# LoRa_Dev_A_1.net
KiCad netlist of a schematic drawn in EAGLE
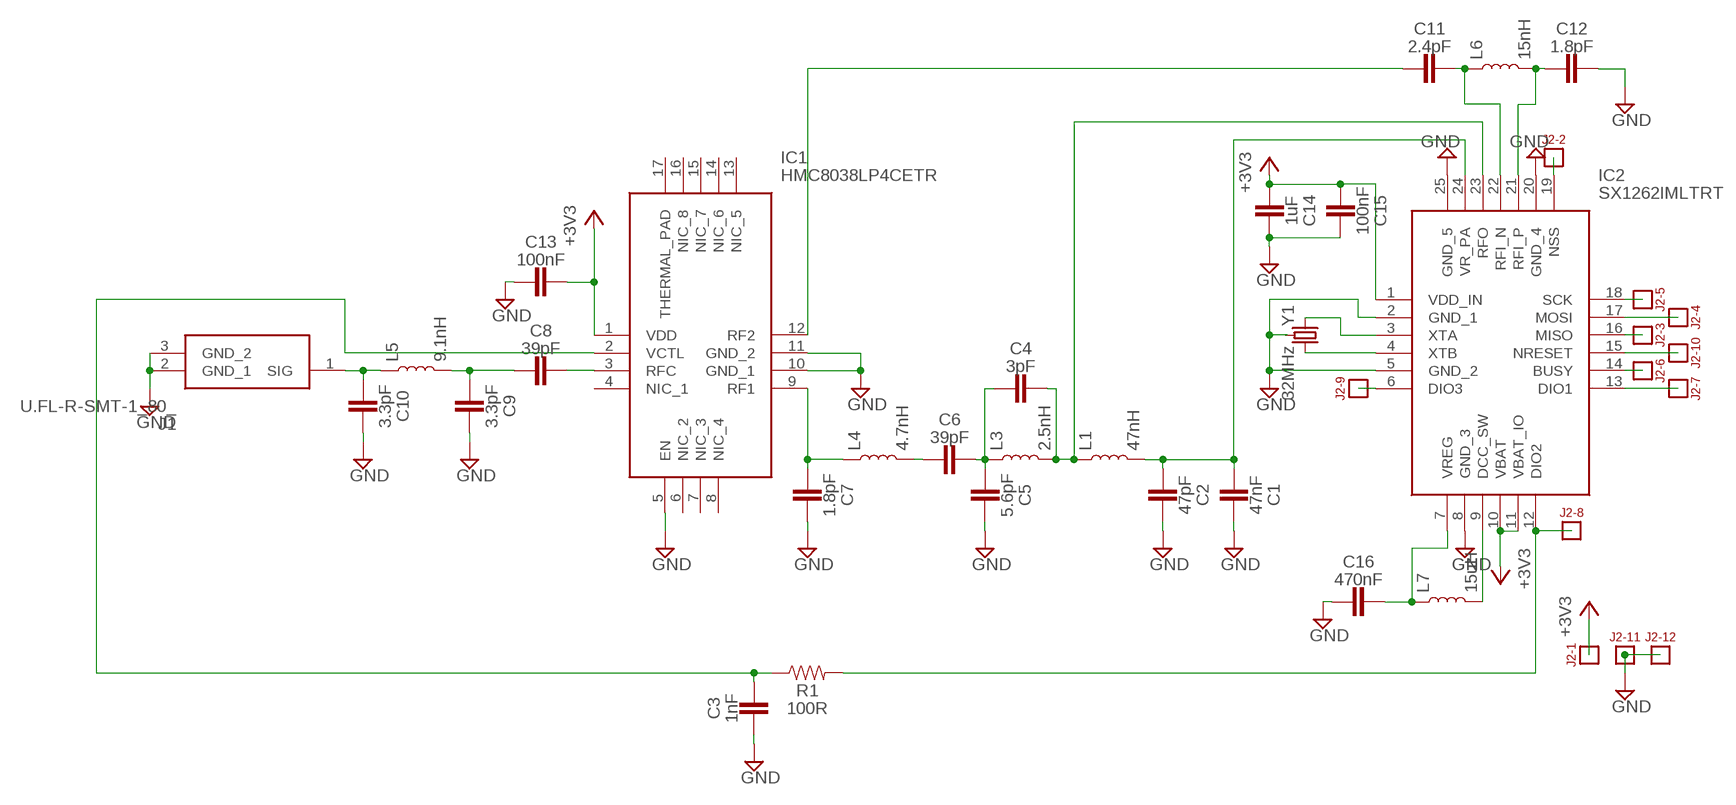
[diagram p0: schematic, sheet 1]

(export (version "E")
  (design (tool "Eeschema 10.0.6"))
  (components
    (comp (ref "C1")
      (value "47nF")
      (footprint "eagle-import:0603")
      (libsource (lib "eagle-import") (part "C_0603"))
    )
    (comp (ref "C2")
      (value "47pF")
      (footprint "eagle-import:0603")
      (libsource (lib "eagle-import") (part "C_0603"))
    )
    (comp (ref "C3")
      (value "1nF")
      (footprint "eagle-import:0603")
      (libsource (lib "eagle-import") (part "C_0603"))
    )
    (comp (ref "C4")
      (value "3pF")
      (footprint "eagle-import:0603")
      (libsource (lib "eagle-import") (part "C_0603"))
    )
    (comp (ref "C5")
      (value "5.6pF")
      (footprint "eagle-import:0402")
      (libsource (lib "eagle-import") (part "C_0402"))
    )
    (comp (ref "C6")
      (value "39pF")
      (footprint "eagle-import:0402")
      (libsource (lib "eagle-import") (part "C_0402"))
    )
    (comp (ref "C7")
      (value "1.8pF")
      (footprint "eagle-import:0402")
      (libsource (lib "eagle-import") (part "C_0402"))
    )
    (comp (ref "C8")
      (value "39pF")
      (footprint "eagle-import:0402")
      (libsource (lib "eagle-import") (part "C_0402"))
    )
    (comp (ref "C9")
      (value "3.3pF")
      (footprint "eagle-import:0402")
      (libsource (lib "eagle-import") (part "C_0402"))
    )
    (comp (ref "C10")
      (value "3.3pF")
      (footprint "eagle-import:0402")
      (libsource (lib "eagle-import") (part "C_0402"))
    )
    (comp (ref "C11")
      (value "2.4pF")
      (footprint "eagle-import:0402")
      (libsource (lib "eagle-import") (part "C_0402"))
    )
    (comp (ref "C12")
      (value "1.8pF")
      (footprint "eagle-import:0402")
      (libsource (lib "eagle-import") (part "C_0402"))
    )
    (comp (ref "C13")
      (value "100nF")
      (footprint "eagle-import:0402")
      (libsource (lib "eagle-import") (part "C_0402"))
    )
    (comp (ref "C14")
      (value "1uF")
      (footprint "eagle-import:0402")
      (libsource (lib "eagle-import") (part "C_0402"))
    )
    (comp (ref "C15")
      (value "100nF")
      (footprint "eagle-import:0402")
      (libsource (lib "eagle-import") (part "C_0402"))
    )
    (comp (ref "C16")
      (value "470nF")
      (footprint "eagle-import:0402")
      (libsource (lib "eagle-import") (part "C_0402"))
    )
    (comp (ref "IC1")
      (value "HMC8038LP4CETR")
      (footprint "eagle-import:QFN65P400X400X90-17N")
      (fields (field (name "MOUSER_PART_NUMBER") "584-HMC8038LP4CETR"))
      (libsource (lib "eagle-import") (part "HMC8038LP4CETR"))
    )
    (comp (ref "IC2")
      (value "SX1262IMLTRT")
      (footprint "eagle-import:QFN50P400X400X100-25N")
      (fields (field (name "MOUSER_PART_NUMBER") "947-SX1262IMLTRT"))
      (libsource (lib "eagle-import") (part "SX1262IMLTRT"))
    )
    (comp (ref "J1")
      (value "U.FL-R-SMT-1_80_")
      (footprint "eagle-import:UFLRSMT180")
      (fields
        (field (name "MANUFACTURER_PART_NUMBER") "U.FL-R-SMT-1(80)")
        (field (name "MOUSER_PART_NUMBER") "798-UFLRSMT180")
      )
      (libsource (lib "eagle-import") (part "U.FL-R-SMT-1_80_"))
    )
    (comp (ref "J2")
      (value "HEADER_12PIN")
      (footprint "eagle-import:HEADER_12PIN")
      (libsource (lib "eagle-import") (part "HEADER_12PIN"))
    )
    (comp (ref "L1")
      (value "47nH")
      (footprint "eagle-import:0603")
      (libsource (lib "eagle-import") (part "L_0603"))
    )
    (comp (ref "L3")
      (value "2.5nH")
      (footprint "eagle-import:0402")
      (libsource (lib "eagle-import") (part "L_0402"))
    )
    (comp (ref "L4")
      (value "4.7nH")
      (footprint "eagle-import:0402")
      (libsource (lib "eagle-import") (part "L_0402"))
    )
    (comp (ref "L5")
      (value "9.1nH")
      (footprint "eagle-import:0402")
      (libsource (lib "eagle-import") (part "L_0402"))
    )
    (comp (ref "L6")
      (value "15nH")
      (footprint "eagle-import:0402")
      (libsource (lib "eagle-import") (part "L_0402"))
    )
    (comp (ref "L7")
      (value "15uH")
      (footprint "eagle-import:0805")
      (libsource (lib "eagle-import") (part "L_0805"))
    )
    (comp (ref "R1")
      (value "100R")
      (footprint "eagle-import:0402")
      (libsource (lib "eagle-import") (part "R_0402"))
    )
    (comp (ref "Y1")
      (value "32MHz")
      (footprint "eagle-import:SMD2016-4P")
      (libsource (lib "eagle-import") (part "XTAL_SMD2016-4P"))
    )
  )
  (nets
    (net (code "1") (name "+3V3") (class "Default")
      (node (ref "C13") (pin "2") (pinfunction "2_2") (pintype "passive"))
      (node (ref "C14") (pin "1") (pinfunction "1_1") (pintype "passive"))
      (node (ref "C15") (pin "1") (pinfunction "1_1") (pintype "passive"))
      (node (ref "IC1") (pin "1") (pinfunction "VDD_1") (pintype "bidirectional"))
      (node (ref "IC2") (pin "1") (pinfunction "VDD_IN_1") (pintype "input"))
      (node (ref "IC2") (pin "10") (pinfunction "VBAT_10") (pintype "input"))
      (node (ref "IC2") (pin "11") (pinfunction "VBAT_IO_11") (pintype "input"))
      (node (ref "J2") (pin "P$1") (pinfunction "P$1_P$1") (pintype "bidirectional"))
    )
    (net (code "2") (name "GND") (class "Default")
      (node (ref "C1") (pin "2") (pinfunction "2_2") (pintype "passive"))
      (node (ref "C10") (pin "2") (pinfunction "2_2") (pintype "passive"))
      (node (ref "C12") (pin "2") (pinfunction "2_2") (pintype "passive"))
      (node (ref "C13") (pin "1") (pinfunction "1_1") (pintype "passive"))
      (node (ref "C14") (pin "2") (pinfunction "2_2") (pintype "passive"))
      (node (ref "C15") (pin "2") (pinfunction "2_2") (pintype "passive"))
      (node (ref "C16") (pin "1") (pinfunction "1_1") (pintype "passive"))
      (node (ref "C2") (pin "2") (pinfunction "2_2") (pintype "passive"))
      (node (ref "C3") (pin "1") (pinfunction "1_1") (pintype "passive"))
      (node (ref "C5") (pin "2") (pinfunction "2_2") (pintype "passive"))
      (node (ref "C7") (pin "2") (pinfunction "2_2") (pintype "passive"))
      (node (ref "C9") (pin "2") (pinfunction "2_2") (pintype "passive"))
      (node (ref "IC1") (pin "10") (pinfunction "GND_1_10") (pintype "bidirectional"))
      (node (ref "IC1") (pin "11") (pinfunction "GND_2_11") (pintype "bidirectional"))
      (node (ref "IC1") (pin "5") (pinfunction "EN_5") (pintype "bidirectional"))
      (node (ref "IC2") (pin "2") (pinfunction "GND_1_2") (pintype "power_in"))
      (node (ref "IC2") (pin "20") (pinfunction "GND_4_20") (pintype "power_in"))
      (node (ref "IC2") (pin "25") (pinfunction "GND_5_25") (pintype "power_in"))
      (node (ref "IC2") (pin "5") (pinfunction "GND_2_5") (pintype "power_in"))
      (node (ref "IC2") (pin "8") (pinfunction "GND_3_8") (pintype "power_in"))
      (node (ref "J1") (pin "2") (pinfunction "GND_1_2") (pintype "bidirectional"))
      (node (ref "J1") (pin "3") (pinfunction "GND_2_3") (pintype "bidirectional"))
      (node (ref "J2") (pin "P$11") (pinfunction "P$1_P$11") (pintype "bidirectional"))
      (node (ref "J2") (pin "P$12") (pinfunction "P$1_P$12") (pintype "bidirectional"))
      (node (ref "Y1") (pin "2") (pinfunction "3_2") (pintype "passive"))
      (node (ref "Y1") (pin "4") (pinfunction "3_4") (pintype "passive"))
    )
    (net (code "3") (name "Net-(C4-Pad1)") (class "Default")
      (node (ref "C4") (pin "1") (pinfunction "1_1") (pintype "passive"))
      (node (ref "C5") (pin "1") (pinfunction "1_1") (pintype "passive"))
      (node (ref "C6") (pin "2") (pinfunction "2_2") (pintype "passive"))
      (node (ref "L3") (pin "1") (pinfunction "1_1") (pintype "passive"))
    )
    (net (code "4") (name "Net-(C6-Pad1)") (class "Default")
      (node (ref "C6") (pin "1") (pinfunction "1_1") (pintype "passive"))
      (node (ref "L4") (pin "2") (pinfunction "2_2") (pintype "passive"))
    )
    (net (code "5") (name "Net-(C8-Pad1)") (class "Default")
      (node (ref "C8") (pin "1") (pinfunction "1_1") (pintype "passive"))
      (node (ref "C9") (pin "1") (pinfunction "1_1") (pintype "passive"))
      (node (ref "L5") (pin "2") (pinfunction "2_2") (pintype "passive"))
    )
    (net (code "6") (name "Net-(IC1-RF1)") (class "Default")
      (node (ref "C7") (pin "1") (pinfunction "1_1") (pintype "passive"))
      (node (ref "IC1") (pin "9") (pinfunction "RF1_9") (pintype "bidirectional"))
      (node (ref "L4") (pin "1") (pinfunction "1_1") (pintype "passive"))
    )
    (net (code "7") (name "Net-(IC1-RF2)") (class "Default")
      (node (ref "C11") (pin "1") (pinfunction "1_1") (pintype "passive"))
      (node (ref "IC1") (pin "12") (pinfunction "RF2_12") (pintype "bidirectional"))
    )
    (net (code "8") (name "Net-(IC1-RFC)") (class "Default")
      (node (ref "C8") (pin "2") (pinfunction "2_2") (pintype "passive"))
      (node (ref "IC1") (pin "3") (pinfunction "RFC_3") (pintype "bidirectional"))
    )
    (net (code "9") (name "Net-(IC1-VCTL)") (class "Default")
      (node (ref "C3") (pin "2") (pinfunction "2_2") (pintype "passive"))
      (node (ref "IC1") (pin "2") (pinfunction "VCTL_2") (pintype "bidirectional"))
      (node (ref "R1") (pin "1") (pinfunction "1_1") (pintype "passive"))
    )
    (net (code "10") (name "Net-(IC2-BUSY)") (class "Default")
      (node (ref "IC2") (pin "14") (pinfunction "BUSY_14") (pintype "bidirectional"))
      (node (ref "J2") (pin "P$6") (pinfunction "P$1_P$6") (pintype "bidirectional"))
    )
    (net (code "11") (name "Net-(IC2-DCC_SW)") (class "Default")
      (node (ref "IC2") (pin "9") (pinfunction "DCC_SW_9") (pintype "output"))
      (node (ref "L7") (pin "2") (pinfunction "2_2") (pintype "passive"))
    )
    (net (code "12") (name "Net-(IC2-DIO1)") (class "Default")
      (node (ref "IC2") (pin "13") (pinfunction "DIO1_13") (pintype "bidirectional"))
      (node (ref "J2") (pin "P$7") (pinfunction "P$1_P$7") (pintype "bidirectional"))
    )
    (net (code "13") (name "Net-(IC2-DIO2)") (class "Default")
      (node (ref "IC2") (pin "12") (pinfunction "DIO2_12") (pintype "bidirectional"))
      (node (ref "J2") (pin "P$8") (pinfunction "P$1_P$8") (pintype "bidirectional"))
      (node (ref "R1") (pin "2") (pinfunction "2_2") (pintype "passive"))
    )
    (net (code "14") (name "Net-(IC2-DIO3)") (class "Default")
      (node (ref "IC2") (pin "6") (pinfunction "DIO3_6") (pintype "bidirectional"))
      (node (ref "J2") (pin "P$9") (pinfunction "P$1_P$9") (pintype "bidirectional"))
    )
    (net (code "15") (name "Net-(IC2-MISO)") (class "Default")
      (node (ref "IC2") (pin "16") (pinfunction "MISO_16") (pintype "output"))
      (node (ref "J2") (pin "P$3") (pinfunction "P$1_P$3") (pintype "bidirectional"))
    )
    (net (code "16") (name "Net-(IC2-MOSI)") (class "Default")
      (node (ref "IC2") (pin "17") (pinfunction "MOSI_17") (pintype "input"))
      (node (ref "J2") (pin "P$4") (pinfunction "P$1_P$4") (pintype "bidirectional"))
    )
    (net (code "17") (name "Net-(IC2-NRESET)") (class "Default")
      (node (ref "IC2") (pin "15") (pinfunction "NRESET_15") (pintype "bidirectional"))
      (node (ref "J2") (pin "P$10") (pinfunction "P$1_P$10") (pintype "bidirectional"))
    )
    (net (code "18") (name "Net-(IC2-NSS)") (class "Default")
      (node (ref "IC2") (pin "19") (pinfunction "NSS_19") (pintype "input"))
      (node (ref "J2") (pin "P$2") (pinfunction "P$1_P$2") (pintype "bidirectional"))
    )
    (net (code "19") (name "Net-(IC2-RFI_N)") (class "Default")
      (node (ref "C11") (pin "2") (pinfunction "2_2") (pintype "passive"))
      (node (ref "IC2") (pin "22") (pinfunction "RFI_N_22") (pintype "input"))
      (node (ref "L6") (pin "1") (pinfunction "1_1") (pintype "passive"))
    )
    (net (code "20") (name "Net-(IC2-RFI_P)") (class "Default")
      (node (ref "C12") (pin "1") (pinfunction "1_1") (pintype "passive"))
      (node (ref "IC2") (pin "21") (pinfunction "RFI_P_21") (pintype "input"))
      (node (ref "L6") (pin "2") (pinfunction "2_2") (pintype "passive"))
    )
    (net (code "21") (name "Net-(IC2-RFO)") (class "Default")
      (node (ref "C4") (pin "2") (pinfunction "2_2") (pintype "passive"))
      (node (ref "IC2") (pin "23") (pinfunction "RFO_23") (pintype "output"))
      (node (ref "L1") (pin "1") (pinfunction "1_1") (pintype "passive"))
      (node (ref "L3") (pin "2") (pinfunction "2_2") (pintype "passive"))
    )
    (net (code "22") (name "Net-(IC2-SCK)") (class "Default")
      (node (ref "IC2") (pin "18") (pinfunction "SCK_18") (pintype "input"))
      (node (ref "J2") (pin "P$5") (pinfunction "P$1_P$5") (pintype "bidirectional"))
    )
    (net (code "23") (name "Net-(IC2-VREG)") (class "Default")
      (node (ref "C16") (pin "2") (pinfunction "2_2") (pintype "passive"))
      (node (ref "IC2") (pin "7") (pinfunction "VREG_7") (pintype "output"))
      (node (ref "L7") (pin "1") (pinfunction "1_1") (pintype "passive"))
    )
    (net (code "24") (name "Net-(IC2-VR_PA)") (class "Default")
      (node (ref "C1") (pin "1") (pinfunction "1_1") (pintype "passive"))
      (node (ref "C2") (pin "1") (pinfunction "1_1") (pintype "passive"))
      (node (ref "IC2") (pin "24") (pinfunction "VR_PA_24") (pintype "bidirectional"))
      (node (ref "L1") (pin "2") (pinfunction "2_2") (pintype "passive"))
    )
    (net (code "25") (name "Net-(IC2-XTA)") (class "Default")
      (node (ref "IC2") (pin "3") (pinfunction "XTA_3") (pintype "input"))
      (node (ref "Y1") (pin "1") (pinfunction "1_1") (pintype "passive"))
    )
    (net (code "26") (name "Net-(IC2-XTB)") (class "Default")
      (node (ref "IC2") (pin "4") (pinfunction "XTB_4") (pintype "input"))
      (node (ref "Y1") (pin "3") (pinfunction "2_3") (pintype "passive"))
    )
    (net (code "27") (name "Net-(J1-SIG)") (class "Default")
      (node (ref "C10") (pin "1") (pinfunction "1_1") (pintype "passive"))
      (node (ref "J1") (pin "1") (pinfunction "SIG_1") (pintype "bidirectional"))
      (node (ref "L5") (pin "1") (pinfunction "1_1") (pintype "passive"))
    )
    (net (code "28") (name "unconnected-(IC1-NIC_1-Pad4)") (class "Default")
      (node (ref "IC1") (pin "4") (pinfunction "NIC_1_4") (pintype "bidirectional"))
    )
    (net (code "29") (name "unconnected-(IC1-NIC_2-Pad6)") (class "Default")
      (node (ref "IC1") (pin "6") (pinfunction "NIC_2_6") (pintype "bidirectional"))
    )
    (net (code "30") (name "unconnected-(IC1-NIC_3-Pad7)") (class "Default")
      (node (ref "IC1") (pin "7") (pinfunction "NIC_3_7") (pintype "bidirectional"))
    )
    (net (code "31") (name "unconnected-(IC1-NIC_4-Pad8)") (class "Default")
      (node (ref "IC1") (pin "8") (pinfunction "NIC_4_8") (pintype "bidirectional"))
    )
    (net (code "32") (name "unconnected-(IC1-NIC_5-Pad13)") (class "Default")
      (node (ref "IC1") (pin "13") (pinfunction "NIC_5_13") (pintype "bidirectional"))
    )
    (net (code "33") (name "unconnected-(IC1-NIC_6-Pad14)") (class "Default")
      (node (ref "IC1") (pin "14") (pinfunction "NIC_6_14") (pintype "bidirectional"))
    )
    (net (code "34") (name "unconnected-(IC1-NIC_7-Pad15)") (class "Default")
      (node (ref "IC1") (pin "15") (pinfunction "NIC_7_15") (pintype "bidirectional"))
    )
    (net (code "35") (name "unconnected-(IC1-NIC_8-Pad16)") (class "Default")
      (node (ref "IC1") (pin "16") (pinfunction "NIC_8_16") (pintype "bidirectional"))
    )
    (net (code "36") (name "unconnected-(IC1-THERMAL_PAD-Pad17)") (class "Default")
      (node (ref "IC1") (pin "17") (pinfunction "THERMAL_PAD_17") (pintype "bidirectional"))
    )
  )
)
